# 4-Ethernet.net
KiCad netlist of a schematic drawn in Altium Designer
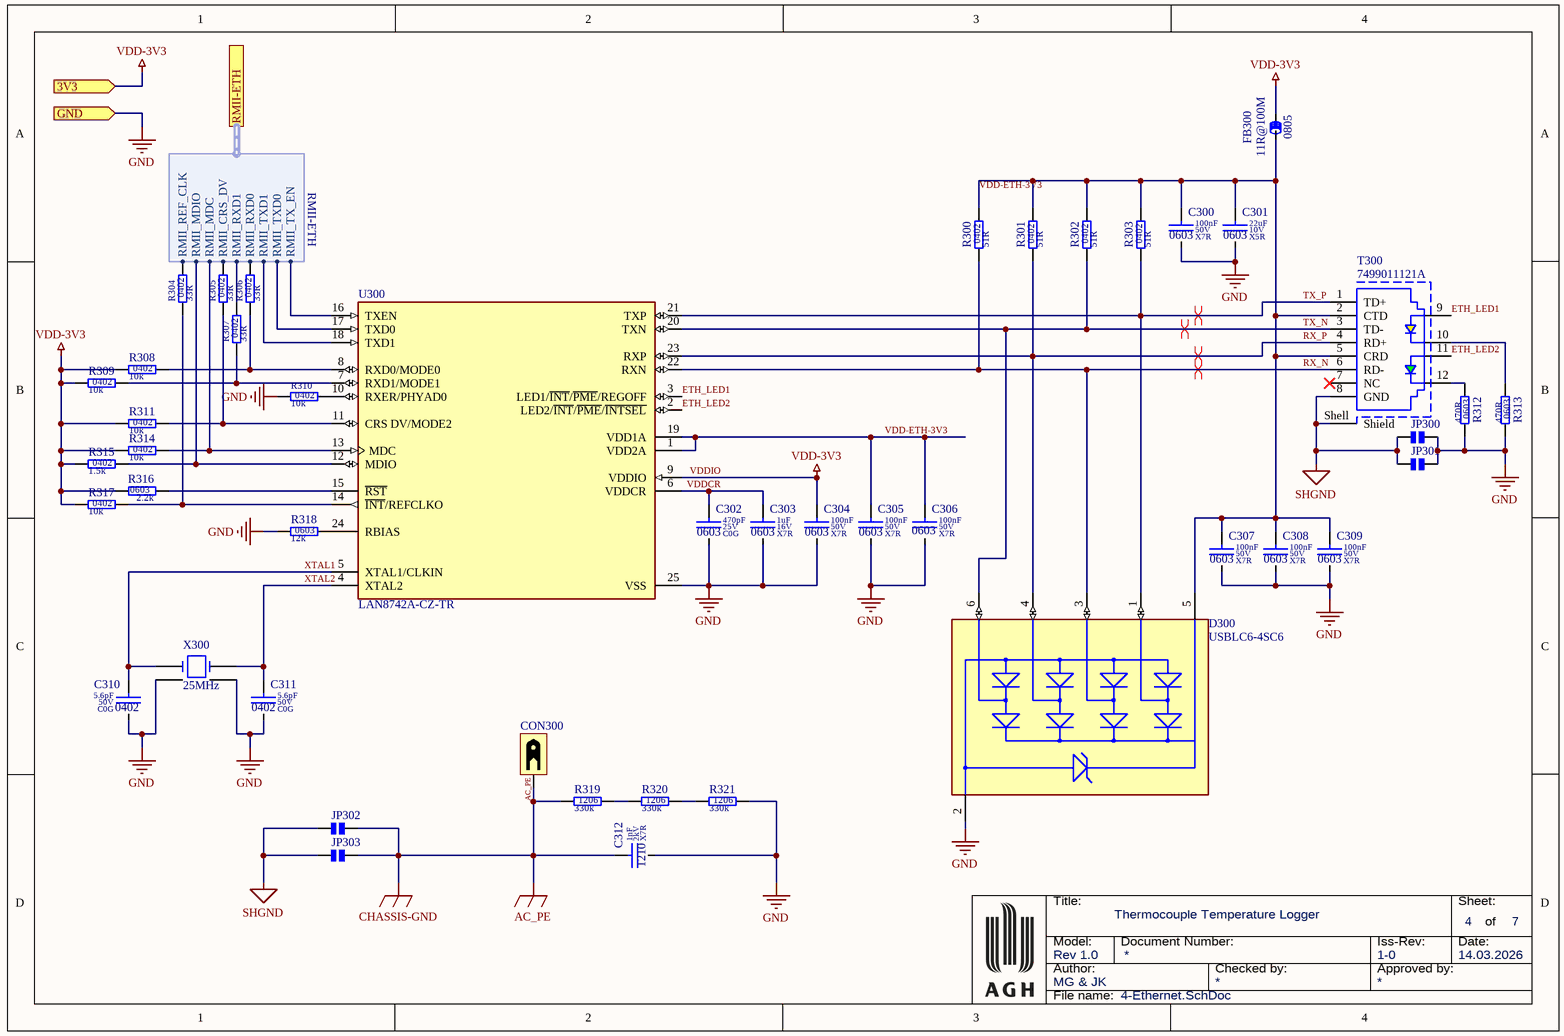
[diagram p0: 4-Ethernet.SchDoc]

(export (version "E")
  (design (tool "Eeschema 10.0.6"))
  (components
    (comp (ref "C300")
      (value "100nF")
      (footprint "C_0603_1608")
      (description "Capacitor")
      (fields
        (field (name "DIELECTRIC") "X7R")
        (field (name "VOLTAGE") "50V")
        (field (name "SCH_FOOTPRINT") "0603")
        (field (name "PART NUMBER") "C_100nF_50V_X7R_0603_10_AECQ1")
        (field (name "MANUFACTURER") "Murata")
      )
      (libsource (lib "Library") (part "C"))
    )
    (comp (ref "C301")
      (value "22uF")
      (footprint "C_0603_1608")
      (description "Capacitor")
      (fields
        (field (name "DIELECTRIC") "X5R")
        (field (name "VOLTAGE") "10V")
        (field (name "SCH_FOOTPRINT") "0603")
        (field (name "PART NUMBER") "C_22uF_10V_X5R_0603_20")
        (field (name "MANUFACTURER") "Murata")
      )
      (libsource (lib "Library") (part "C"))
    )
    (comp (ref "C302")
      (value "470pF")
      (footprint "C_0603_1608")
      (description "Capacitor")
      (fields
        (field (name "DIELECTRIC") "C0G")
        (field (name "VOLTAGE") "25V")
        (field (name "SCH_FOOTPRINT") "0603")
        (field (name "PART NUMBER") "C_470pF_25V_C0G_0603_5")
        (field (name "MANUFACTURER") "Wurth Elektronik")
      )
      (libsource (lib "Library") (part "C"))
    )
    (comp (ref "C303")
      (value "1uF")
      (footprint "C_0603_1608")
      (description "Capacitor")
      (fields
        (field (name "DIELECTRIC") "X7R")
        (field (name "VOLTAGE") "16V")
        (field (name "SCH_FOOTPRINT") "0603")
        (field (name "PART NUMBER") "C_1uF_16V_X7R_0603_10")
        (field (name "MANUFACTURER") "Wurth Elektronik")
      )
      (libsource (lib "Library") (part "C"))
    )
    (comp (ref "C304")
      (value "100nF")
      (footprint "C_0603_1608")
      (description "Capacitor")
      (fields
        (field (name "DIELECTRIC") "X7R")
        (field (name "VOLTAGE") "50V")
        (field (name "SCH_FOOTPRINT") "0603")
        (field (name "PART NUMBER") "C_100nF_50V_X7R_0603_10_AECQ1")
        (field (name "MANUFACTURER") "Murata")
      )
      (libsource (lib "Library") (part "C"))
    )
    (comp (ref "C305")
      (value "100nF")
      (footprint "C_0603_1608")
      (description "Capacitor")
      (fields
        (field (name "DIELECTRIC") "X7R")
        (field (name "VOLTAGE") "50V")
        (field (name "SCH_FOOTPRINT") "0603")
        (field (name "PART NUMBER") "C_100nF_50V_X7R_0603_10_AECQ1")
        (field (name "MANUFACTURER") "Murata")
      )
      (libsource (lib "Library") (part "C"))
    )
    (comp (ref "C306")
      (value "100nF")
      (footprint "C_0603_1608")
      (description "Capacitor")
      (fields
        (field (name "DIELECTRIC") "X7R")
        (field (name "VOLTAGE") "50V")
        (field (name "SCH_FOOTPRINT") "0603")
        (field (name "PART NUMBER") "C_100nF_50V_X7R_0603_10_AECQ1")
        (field (name "MANUFACTURER") "Murata")
      )
      (libsource (lib "Library") (part "C"))
    )
    (comp (ref "C307")
      (value "100nF")
      (footprint "C_0603_1608")
      (description "Capacitor")
      (fields
        (field (name "DIELECTRIC") "X7R")
        (field (name "VOLTAGE") "50V")
        (field (name "SCH_FOOTPRINT") "0603")
        (field (name "PART NUMBER") "C_100nF_50V_X7R_0603_10_AECQ1")
        (field (name "MANUFACTURER") "Murata")
      )
      (libsource (lib "Library") (part "C"))
    )
    (comp (ref "C308")
      (value "100nF")
      (footprint "C_0603_1608")
      (description "Capacitor")
      (fields
        (field (name "DIELECTRIC") "X7R")
        (field (name "VOLTAGE") "50V")
        (field (name "SCH_FOOTPRINT") "0603")
        (field (name "PART NUMBER") "C_100nF_50V_X7R_0603_10_AECQ1")
        (field (name "MANUFACTURER") "Murata")
      )
      (libsource (lib "Library") (part "C"))
    )
    (comp (ref "C309")
      (value "100nF")
      (footprint "C_0603_1608")
      (description "Capacitor")
      (fields
        (field (name "DIELECTRIC") "X7R")
        (field (name "VOLTAGE") "50V")
        (field (name "SCH_FOOTPRINT") "0603")
        (field (name "PART NUMBER") "C_100nF_50V_X7R_0603_10_AECQ1")
        (field (name "MANUFACTURER") "Murata")
      )
      (libsource (lib "Library") (part "C"))
    )
    (comp (ref "C310")
      (value "5.6pF")
      (footprint "C_0402_1005")
      (description "Capacitor")
      (fields
        (field (name "DIELECTRIC") "C0G")
        (field (name "VOLTAGE") "50V")
        (field (name "SCH_FOOTPRINT") "0402")
        (field (name "PART NUMBER") "C_5.6pF_50V_C0G_0402_2_AECQ1")
        (field (name "MANUFACTURER") "Murata")
      )
      (libsource (lib "Library") (part "C"))
    )
    (comp (ref "C311")
      (value "5.6pF")
      (footprint "C_0402_1005")
      (description "Capacitor")
      (fields
        (field (name "DIELECTRIC") "C0G")
        (field (name "VOLTAGE") "50V")
        (field (name "SCH_FOOTPRINT") "0402")
        (field (name "PART NUMBER") "C_5.6pF_50V_C0G_0402_2_AECQ1")
        (field (name "MANUFACTURER") "Murata")
      )
      (libsource (lib "Library") (part "C"))
    )
    (comp (ref "C312")
      (value "1nF")
      (footprint "C_1210_3225")
      (description "Capacitor")
      (fields
        (field (name "DIELECTRIC") "X7R")
        (field (name "VOLTAGE") "2kV")
        (field (name "SCH_FOOTPRINT") "1210")
        (field (name "PART NUMBER") "C_1nF_2kV_X7R_1210_10")
        (field (name "MANUFACTURER") "AVX")
      )
      (libsource (lib "Library") (part "C"))
    )
    (comp (ref "CON300")
      (value "Terminal for PE")
      (footprint "TP_1-726388-2")
      (description "Terminal")
      (fields
        (field (name "PART NUMBER") "TP_TERMINAL_1-726388-2")
        (field (name "MANUFACTURER") "TE Connectivity")
      )
      (libsource (lib "Library") (part "TP_TERMINAL"))
    )
    (comp (ref "D300")
      (value "USBLC6-4SC6")
      (footprint "FP-SOT23-6L-MFG")
      (description "TVS DIODE 5.25V 17V SOT23-6")
      (fields
        (field (name "MANUFACTURER") "STMicroelectronics")
        (field (name "OCTOPART") "https://octopart.com/usblc6-4sc6-stmicroelectronics-347147")
      )
      (libsource (lib "Altium Content Vault") (part "3e70b616ccdc4c88b528e1820c4a7da"))
    )
    (comp (ref "FB300")
      (value "11R@100M")
      (footprint "FB_0805_2012")
      (description "Ferrite Bead")
      (fields
        (field (name "SCH_FOOTPRINT") "0805")
        (field (name "PART NUMBER") "FB_2508051107Y0")
        (field (name "MANUFACTURER") "Fair-Rite")
      )
      (libsource (lib "Library") (part "FB"))
    )
    (comp (ref "JP300")
      (value "Solder Jumper 0603/1608")
      (footprint "JP_0603_1608")
      (fields (field (name "PART NUMBER") "JP_0603_1608"))
      (libsource (lib "Library") (part "JP"))
    )
    (comp (ref "JP301")
      (value "Solder Jumper 0603/1608")
      (footprint "JP_0603_1608")
      (fields (field (name "PART NUMBER") "JP_0603_1608"))
      (libsource (lib "Library") (part "JP"))
    )
    (comp (ref "JP302")
      (value "Solder Jumper 0603/1608")
      (footprint "JP_0603_1608")
      (fields (field (name "PART NUMBER") "JP_0603_1608"))
      (libsource (lib "Library") (part "JP"))
    )
    (comp (ref "JP303")
      (value "Solder Jumper 0603/1608")
      (footprint "JP_0603_1608")
      (fields (field (name "PART NUMBER") "JP_0603_1608"))
      (libsource (lib "Library") (part "JP"))
    )
    (comp (ref "R300")
      (value "51R")
      (footprint "R_0402_1005")
      (fields
        (field (name "SCH_FOOTPRINT") "0402")
        (field (name "PART NUMBER") "R_51R_0402_1_AECQ0")
        (field (name "VOLTAGE") "50V")
        (field (name "POWER") "100mW")
      )
      (libsource (lib "Library") (part "R"))
    )
    (comp (ref "R301")
      (value "51R")
      (footprint "R_0402_1005")
      (fields
        (field (name "SCH_FOOTPRINT") "0402")
        (field (name "PART NUMBER") "R_51R_0402_1_AECQ0")
        (field (name "VOLTAGE") "50V")
        (field (name "POWER") "100mW")
      )
      (libsource (lib "Library") (part "R"))
    )
    (comp (ref "R302")
      (value "51R")
      (footprint "R_0402_1005")
      (fields
        (field (name "SCH_FOOTPRINT") "0402")
        (field (name "PART NUMBER") "R_51R_0402_1_AECQ0")
        (field (name "VOLTAGE") "50V")
        (field (name "POWER") "100mW")
      )
      (libsource (lib "Library") (part "R"))
    )
    (comp (ref "R303")
      (value "51R")
      (footprint "R_0402_1005")
      (fields
        (field (name "SCH_FOOTPRINT") "0402")
        (field (name "PART NUMBER") "R_51R_0402_1_AECQ0")
        (field (name "VOLTAGE") "50V")
        (field (name "POWER") "100mW")
      )
      (libsource (lib "Library") (part "R"))
    )
    (comp (ref "R304")
      (value "33R")
      (footprint "R_0402_1005")
      (fields
        (field (name "SCH_FOOTPRINT") "0402")
        (field (name "PART NUMBER") "R_33R_0402_1_AECQ0")
        (field (name "VOLTAGE") "50V")
        (field (name "POWER") "100mW")
      )
      (libsource (lib "Library") (part "R"))
    )
    (comp (ref "R305")
      (value "33R")
      (footprint "R_0402_1005")
      (fields
        (field (name "SCH_FOOTPRINT") "0402")
        (field (name "PART NUMBER") "R_33R_0402_1_AECQ0")
        (field (name "VOLTAGE") "50V")
        (field (name "POWER") "100mW")
      )
      (libsource (lib "Library") (part "R"))
    )
    (comp (ref "R306")
      (value "33R")
      (footprint "R_0402_1005")
      (fields
        (field (name "SCH_FOOTPRINT") "0402")
        (field (name "PART NUMBER") "R_33R_0402_1_AECQ0")
        (field (name "VOLTAGE") "50V")
        (field (name "POWER") "100mW")
      )
      (libsource (lib "Library") (part "R"))
    )
    (comp (ref "R307")
      (value "33R")
      (footprint "R_0402_1005")
      (fields
        (field (name "SCH_FOOTPRINT") "0402")
        (field (name "PART NUMBER") "R_33R_0402_1_AECQ0")
        (field (name "VOLTAGE") "50V")
        (field (name "POWER") "100mW")
      )
      (libsource (lib "Library") (part "R"))
    )
    (comp (ref "R308")
      (value "10k")
      (footprint "R_0402_1005")
      (fields
        (field (name "SCH_FOOTPRINT") "0402")
        (field (name "PART NUMBER") "R_10k_0402_1")
        (field (name "VOLTAGE") "50V")
        (field (name "POWER") "63mW")
      )
      (libsource (lib "Library") (part "R"))
    )
    (comp (ref "R309")
      (value "10k")
      (footprint "R_0402_1005")
      (fields
        (field (name "SCH_FOOTPRINT") "0402")
        (field (name "PART NUMBER") "R_10k_0402_1")
        (field (name "VOLTAGE") "50V")
        (field (name "POWER") "63mW")
      )
      (libsource (lib "Library") (part "R"))
    )
    (comp (ref "R310")
      (value "10k")
      (footprint "R_0402_1005")
      (fields
        (field (name "SCH_FOOTPRINT") "0402")
        (field (name "PART NUMBER") "R_10k_0402_1")
        (field (name "VOLTAGE") "50V")
        (field (name "POWER") "63mW")
      )
      (libsource (lib "Library") (part "R"))
    )
    (comp (ref "R311")
      (value "10k")
      (footprint "R_0402_1005")
      (fields
        (field (name "SCH_FOOTPRINT") "0402")
        (field (name "PART NUMBER") "R_10k_0402_1")
        (field (name "VOLTAGE") "50V")
        (field (name "POWER") "63mW")
      )
      (libsource (lib "Library") (part "R"))
    )
    (comp (ref "R312")
      (value "470R")
      (footprint "R_0603_1608")
      (fields
        (field (name "SCH_FOOTPRINT") "0603")
        (field (name "PART NUMBER") "R_470R_0603_1")
        (field (name "VOLTAGE") "50V")
        (field (name "POWER") "100mW")
      )
      (libsource (lib "Library") (part "R"))
    )
    (comp (ref "R313")
      (value "470R")
      (footprint "R_0603_1608")
      (fields
        (field (name "SCH_FOOTPRINT") "0603")
        (field (name "PART NUMBER") "R_470R_0603_1")
        (field (name "VOLTAGE") "50V")
        (field (name "POWER") "100mW")
      )
      (libsource (lib "Library") (part "R"))
    )
    (comp (ref "R314")
      (value "10k")
      (footprint "R_0402_1005")
      (fields
        (field (name "SCH_FOOTPRINT") "0402")
        (field (name "PART NUMBER") "R_10k_0402_1")
        (field (name "VOLTAGE") "50V")
        (field (name "POWER") "63mW")
      )
      (libsource (lib "Library") (part "R"))
    )
    (comp (ref "R315")
      (value "1.5k")
      (footprint "R_0402_1005")
      (fields
        (field (name "SCH_FOOTPRINT") "0402")
        (field (name "PART NUMBER") "R_1.5k_0402_1_AECQ0")
        (field (name "VOLTAGE") "50V")
        (field (name "POWER") "100mW")
      )
      (libsource (lib "Library") (part "R"))
    )
    (comp (ref "R316")
      (value "2.2k")
      (footprint "R_0603_1608")
      (fields
        (field (name "SCH_FOOTPRINT") "0603")
        (field (name "PART NUMBER") "R_2.2k_0603_1")
        (field (name "VOLTAGE") "50V")
        (field (name "POWER") "100mW")
      )
      (libsource (lib "Library") (part "R"))
    )
    (comp (ref "R317")
      (value "10k")
      (footprint "R_0402_1005")
      (fields
        (field (name "SCH_FOOTPRINT") "0402")
        (field (name "PART NUMBER") "R_10k_0402_1")
        (field (name "VOLTAGE") "50V")
        (field (name "POWER") "63mW")
      )
      (libsource (lib "Library") (part "R"))
    )
    (comp (ref "R318")
      (value "12k")
      (footprint "R_0603_1608")
      (fields
        (field (name "SCH_FOOTPRINT") "0603")
        (field (name "PART NUMBER") "R_12k_0603_1")
        (field (name "VOLTAGE") "50V")
        (field (name "POWER") "100mW")
      )
      (libsource (lib "Library") (part "R"))
    )
    (comp (ref "R319")
      (value "330k")
      (footprint "R_1206_3216")
      (fields
        (field (name "SCH_FOOTPRINT") "1206")
        (field (name "PART NUMBER") "R_330k_1206_1")
        (field (name "VOLTAGE") "200V")
        (field (name "POWER") "250mW")
      )
      (libsource (lib "Library") (part "R"))
    )
    (comp (ref "R320")
      (value "330k")
      (footprint "R_1206_3216")
      (fields
        (field (name "SCH_FOOTPRINT") "1206")
        (field (name "PART NUMBER") "R_330k_1206_1")
        (field (name "VOLTAGE") "200V")
        (field (name "POWER") "250mW")
      )
      (libsource (lib "Library") (part "R"))
    )
    (comp (ref "R321")
      (value "330k")
      (footprint "R_1206_3216")
      (fields
        (field (name "SCH_FOOTPRINT") "1206")
        (field (name "PART NUMBER") "R_330k_1206_1")
        (field (name "VOLTAGE") "200V")
        (field (name "POWER") "250mW")
      )
      (libsource (lib "Library") (part "R"))
    )
    (comp (ref "T300")
      (value "7499011121A")
      (footprint "7499011121A")
      (description "WE-RJ45 LAN Transformer, THT, 10/100 Base-T, Tab Down, 1 Port")
      (fields (field (name "MANUFACTURER") "Wurth Elektronik"))
      (libsource (lib "Altium_WE-RJ45 LAN (rev25d)") (part "7499011121A"))
    )
    (comp (ref "U300")
      (value "LAN8742A-CZ-TR")
      (footprint "FP-C04-143B-S4QFN-MFG")
      (description "IC TRANSCEIVER 1/1 24SQFN")
      (fields
        (field (name "MANUFACTURER") "Microchip")
        (field (name "OCTOPART") "https://octopart.com/lan8742a-cz-tr-microchip-29030587")
      )
      (libsource (lib "Altium Content Vault") (part "83151231c1ada07e85dcda6cce77793"))
    )
    (comp (ref "X300")
      (value "25MHz")
      (footprint "X_2x1.6_4PIN")
      (fields
        (field (name "PART NUMBER") "NX2016SA-25.000M-STD-CZS-1")
        (field (name "MANUFACTURER") "NDK")
        (field (name "Comment") "32 MHz Oscilator")
      )
      (libsource (lib "Library") (part "X_GENERIC_4PIN"))
    )
  )
  (nets
    (net (code "2") (name "/ETH_LED1") (class "Default")
      (node (ref "T300") (pin "9") (pinfunction "9_9") (pintype "passive"))
      (node (ref "U300") (pin "3") (pinfunction "LED1/~{INT}/~{PME}/REGOFF_3") (pintype "bidirectional"))
    )
    (net (code "3") (name "/ETH_LED2") (class "Default")
      (node (ref "T300") (pin "11") (pinfunction "11_11") (pintype "passive"))
      (node (ref "U300") (pin "2") (pinfunction "LED2/~{INT}/~{PME}/~{INTSEL}_2") (pintype "bidirectional"))
    )
    (net (code "4") (name "/RMII_CRS_DV") (class "Default")
      (node (ref "R305") (pin "2") (pinfunction "2_2") (pintype "passive"))
    )
    (net (code "5") (name "/RMII_MDC") (class "Default")
      (node (ref "R314") (pin "2") (pinfunction "2_2") (pintype "passive"))
      (node (ref "U300") (pin "13") (pinfunction "MDC_13") (pintype "input"))
    )
    (net (code "6") (name "/RMII_MDIO") (class "Default")
      (node (ref "R315") (pin "2") (pinfunction "2_2") (pintype "passive"))
      (node (ref "U300") (pin "12") (pinfunction "MDIO_12") (pintype "bidirectional"))
    )
    (net (code "7") (name "/RMII_REF_CLK") (class "Default")
      (node (ref "R304") (pin "2") (pinfunction "2_2") (pintype "passive"))
    )
    (net (code "8") (name "/RMII_RXD0") (class "Default")
      (node (ref "R306") (pin "2") (pinfunction "2_2") (pintype "passive"))
    )
    (net (code "9") (name "/RMII_RXD1") (class "Default")
      (node (ref "R307") (pin "2") (pinfunction "2_2") (pintype "passive"))
    )
    (net (code "10") (name "/RMII_TXD0") (class "Default")
      (node (ref "U300") (pin "17") (pinfunction "TXD0_17") (pintype "input"))
    )
    (net (code "11") (name "/RMII_TXD1") (class "Default")
      (node (ref "U300") (pin "18") (pinfunction "TXD1_18") (pintype "input"))
    )
    (net (code "12") (name "/RMII_TX_EN") (class "Default")
      (node (ref "U300") (pin "16") (pinfunction "TXEN_16") (pintype "input"))
    )
    (net (code "13") (name "/RX_N") (class "Default")
      (node (ref "D300") (pin "3") (pinfunction "I/O2_3") (pintype "bidirectional"))
      (node (ref "R300") (pin "1") (pinfunction "1_1") (pintype "passive"))
      (node (ref "T300") (pin "6") (pinfunction "RD-_6") (pintype "passive"))
      (node (ref "U300") (pin "22") (pinfunction "RXN_22") (pintype "bidirectional"))
    )
    (net (code "14") (name "/RX_P") (class "Default")
      (node (ref "D300") (pin "4") (pinfunction "I/O3_4") (pintype "bidirectional"))
      (node (ref "R301") (pin "1") (pinfunction "1_1") (pintype "passive"))
      (node (ref "T300") (pin "4") (pinfunction "RD+_4") (pintype "passive"))
      (node (ref "U300") (pin "23") (pinfunction "RXP_23") (pintype "bidirectional"))
    )
    (net (code "15") (name "/TX_N") (class "Default")
      (node (ref "D300") (pin "6") (pinfunction "I/O4_6") (pintype "bidirectional"))
      (node (ref "R302") (pin "1") (pinfunction "1_1") (pintype "passive"))
      (node (ref "T300") (pin "3") (pinfunction "TD-_3") (pintype "passive"))
      (node (ref "U300") (pin "20") (pinfunction "TXN_20") (pintype "bidirectional"))
    )
    (net (code "16") (name "/TX_P") (class "Default")
      (node (ref "D300") (pin "1") (pinfunction "I/O1_1") (pintype "bidirectional"))
      (node (ref "R303") (pin "1") (pinfunction "1_1") (pintype "passive"))
      (node (ref "T300") (pin "1") (pinfunction "TD+_1") (pintype "passive"))
      (node (ref "U300") (pin "21") (pinfunction "TXP_21") (pintype "bidirectional"))
    )
    (net (code "17") (name "/VDD-ETH-3V3") (class "Default")
      (node (ref "C300") (pin "1") (pinfunction "1_1") (pintype "passive"))
      (node (ref "C301") (pin "1") (pinfunction "1_1") (pintype "passive"))
      (node (ref "C305") (pin "1") (pinfunction "1_1") (pintype "passive"))
      (node (ref "C306") (pin "1") (pinfunction "1_1") (pintype "passive"))
      (node (ref "C307") (pin "1") (pinfunction "1_1") (pintype "passive"))
      (node (ref "C308") (pin "1") (pinfunction "1_1") (pintype "passive"))
      (node (ref "C309") (pin "1") (pinfunction "1_1") (pintype "passive"))
      (node (ref "D300") (pin "5") (pinfunction "VBUS_5") (pintype "power_in"))
      (node (ref "FB300") (pin "2") (pintype "passive"))
      (node (ref "R300") (pin "2") (pinfunction "2_2") (pintype "passive"))
      (node (ref "R301") (pin "2") (pinfunction "2_2") (pintype "passive"))
      (node (ref "R302") (pin "2") (pinfunction "2_2") (pintype "passive"))
      (node (ref "R303") (pin "2") (pinfunction "2_2") (pintype "passive"))
      (node (ref "T300") (pin "2") (pinfunction "CTD_2") (pintype "passive"))
      (node (ref "T300") (pin "5") (pinfunction "CRD_5") (pintype "passive"))
      (node (ref "U300") (pin "1") (pinfunction "VDD2A_1") (pintype "power_in"))
      (node (ref "U300") (pin "19") (pinfunction "VDD1A_19") (pintype "power_in"))
    )
    (net (code "18") (name "/VDDCR") (class "Default")
      (node (ref "C302") (pin "1") (pinfunction "1_1") (pintype "passive"))
      (node (ref "C303") (pin "1") (pinfunction "1_1") (pintype "passive"))
      (node (ref "U300") (pin "6") (pinfunction "VDDCR_6") (pintype "power_in"))
    )
    (net (code "19") (name "/XTAL1") (class "Default")
      (node (ref "C310") (pin "1") (pinfunction "1_1") (pintype "passive"))
      (node (ref "U300") (pin "5") (pinfunction "XTAL1/CLKIN_5") (pintype "passive"))
      (node (ref "X300") (pin "3") (pinfunction "3_3") (pintype "passive"))
    )
    (net (code "20") (name "/XTAL2") (class "Default")
      (node (ref "C311") (pin "1") (pinfunction "1_1") (pintype "passive"))
      (node (ref "U300") (pin "4") (pinfunction "XTAL2_4") (pintype "passive"))
      (node (ref "X300") (pin "1") (pinfunction "1_1") (pintype "passive"))
    )
    (net (code "22") (name "AC_PE") (class "Default")
      (node (ref "C312") (pin "1") (pinfunction "1_1") (pintype "passive"))
      (node (ref "CON300") (pin "1") (pinfunction "TP_1") (pintype "passive"))
      (node (ref "JP302") (pin "2") (pinfunction "2_2") (pintype "passive"))
      (node (ref "JP303") (pin "2") (pinfunction "2_2") (pintype "passive"))
      (node (ref "R319") (pin "1") (pinfunction "1_1") (pintype "passive"))
    )
    (net (code "23") (name "GND") (class "Default")
      (node (ref "C300") (pin "2") (pinfunction "2_2") (pintype "passive"))
      (node (ref "C301") (pin "2") (pinfunction "2_2") (pintype "passive"))
      (node (ref "C302") (pin "2") (pinfunction "2_2") (pintype "passive"))
      (node (ref "C303") (pin "2") (pinfunction "2_2") (pintype "passive"))
      (node (ref "C304") (pin "2") (pinfunction "2_2") (pintype "passive"))
      (node (ref "C305") (pin "2") (pinfunction "2_2") (pintype "passive"))
      (node (ref "C306") (pin "2") (pinfunction "2_2") (pintype "passive"))
      (node (ref "C307") (pin "2") (pinfunction "2_2") (pintype "passive"))
      (node (ref "C308") (pin "2") (pinfunction "2_2") (pintype "passive"))
      (node (ref "C309") (pin "2") (pinfunction "2_2") (pintype "passive"))
      (node (ref "C310") (pin "2") (pinfunction "2_2") (pintype "passive"))
      (node (ref "C311") (pin "2") (pinfunction "2_2") (pintype "passive"))
      (node (ref "C312") (pin "2") (pinfunction "2_2") (pintype "passive"))
      (node (ref "D300") (pin "2") (pinfunction "GND_2") (pintype "passive"))
      (node (ref "JP300") (pin "2") (pinfunction "2_2") (pintype "passive"))
      (node (ref "JP301") (pin "2") (pinfunction "2_2") (pintype "passive"))
      (node (ref "R310") (pin "1") (pinfunction "1_1") (pintype "passive"))
      (node (ref "R312") (pin "1") (pinfunction "1_1") (pintype "passive"))
      (node (ref "R313") (pin "1") (pinfunction "1_1") (pintype "passive"))
      (node (ref "R318") (pin "1") (pinfunction "1_1") (pintype "passive"))
      (node (ref "R321") (pin "2") (pinfunction "2_2") (pintype "passive"))
      (node (ref "U300") (pin "25") (pinfunction "VSS_25") (pintype "passive"))
      (node (ref "X300") (pin "2") (pinfunction "GND_2") (pintype "passive"))
      (node (ref "X300") (pin "4") (pinfunction "GND_4") (pintype "passive"))
    )
    (net (code "24") (name "Net-(R312-Pad2)") (class "Default")
      (node (ref "R312") (pin "2") (pinfunction "2_2") (pintype "passive"))
      (node (ref "T300") (pin "12") (pinfunction "12_12") (pintype "passive"))
    )
    (net (code "25") (name "Net-(R313-Pad2)") (class "Default")
      (node (ref "R313") (pin "2") (pinfunction "2_2") (pintype "passive"))
      (node (ref "T300") (pin "10") (pinfunction "10_10") (pintype "passive"))
    )
    (net (code "26") (name "Net-(R319-Pad2)") (class "Default")
      (node (ref "R319") (pin "2") (pinfunction "2_2") (pintype "passive"))
      (node (ref "R320") (pin "1") (pinfunction "1_1") (pintype "passive"))
    )
    (net (code "27") (name "Net-(R320-Pad2)") (class "Default")
      (node (ref "R320") (pin "2") (pinfunction "2_2") (pintype "passive"))
      (node (ref "R321") (pin "1") (pinfunction "1_1") (pintype "passive"))
    )
    (net (code "28") (name "Net-(U300-CRS_DV{slash}MODE2)") (class "Default")
      (node (ref "R305") (pin "1") (pinfunction "1_1") (pintype "passive"))
      (node (ref "R311") (pin "2") (pinfunction "2_2") (pintype "passive"))
      (node (ref "U300") (pin "11") (pinfunction "CRS_DV/MODE2_11") (pintype "bidirectional"))
    )
    (net (code "29") (name "Net-(U300-RBIAS)") (class "Default")
      (node (ref "R318") (pin "2") (pinfunction "2_2") (pintype "passive"))
      (node (ref "U300") (pin "24") (pinfunction "RBIAS_24") (pintype "passive"))
    )
    (net (code "30") (name "Net-(U300-RXD0{slash}MODE0)") (class "Default")
      (node (ref "R306") (pin "1") (pinfunction "1_1") (pintype "passive"))
      (node (ref "R308") (pin "2") (pinfunction "2_2") (pintype "passive"))
      (node (ref "U300") (pin "8") (pinfunction "RXD0/MODE0_8") (pintype "bidirectional"))
    )
    (net (code "31") (name "Net-(U300-RXD1{slash}MODE1)") (class "Default")
      (node (ref "R307") (pin "1") (pinfunction "1_1") (pintype "passive"))
      (node (ref "R309") (pin "2") (pinfunction "2_2") (pintype "passive"))
      (node (ref "U300") (pin "7") (pinfunction "RXD1/MODE1_7") (pintype "bidirectional"))
    )
    (net (code "32") (name "Net-(U300-RXER{slash}PHYAD0)") (class "Default")
      (node (ref "R310") (pin "2") (pinfunction "2_2") (pintype "passive"))
      (node (ref "U300") (pin "10") (pinfunction "RXER/PHYAD0_10") (pintype "bidirectional"))
    )
    (net (code "33") (name "Net-(U300-~{INT}{slash}REFCLKO)") (class "Default")
      (node (ref "R304") (pin "1") (pinfunction "1_1") (pintype "passive"))
      (node (ref "R317") (pin "2") (pinfunction "2_2") (pintype "passive"))
      (node (ref "U300") (pin "14") (pinfunction "~{INT}/REFCLKO_14") (pintype "output"))
    )
    (net (code "34") (name "Net-(U300-~{RST})") (class "Default")
      (node (ref "R316") (pin "1") (pinfunction "1_1") (pintype "passive"))
      (node (ref "U300") (pin "15") (pinfunction "~{RST}_15") (pintype "passive"))
    )
    (net (code "35") (name "SHGND") (class "Default")
      (node (ref "JP300") (pin "1") (pinfunction "1_1") (pintype "passive"))
      (node (ref "JP301") (pin "1") (pinfunction "1_1") (pintype "passive"))
      (node (ref "JP302") (pin "1") (pinfunction "1_1") (pintype "passive"))
      (node (ref "JP303") (pin "1") (pinfunction "1_1") (pintype "passive"))
      (node (ref "T300") (pin "8") (pinfunction "GND_8") (pintype "passive"))
      (node (ref "T300") (pin "Shell") (pinfunction "Shield_Shell") (pintype "passive"))
    )
    (net (code "36") (name "VDD-3V3") (class "Default")
      (node (ref "C304") (pin "1") (pinfunction "1_1") (pintype "passive"))
      (node (ref "FB300") (pin "1") (pintype "passive"))
      (node (ref "R308") (pin "1") (pinfunction "1_1") (pintype "passive"))
      (node (ref "R309") (pin "1") (pinfunction "1_1") (pintype "passive"))
      (node (ref "R311") (pin "1") (pinfunction "1_1") (pintype "passive"))
      (node (ref "R314") (pin "1") (pinfunction "1_1") (pintype "passive"))
      (node (ref "R315") (pin "1") (pinfunction "1_1") (pintype "passive"))
      (node (ref "R316") (pin "2") (pinfunction "2_2") (pintype "passive"))
      (node (ref "R317") (pin "1") (pinfunction "1_1") (pintype "passive"))
      (node (ref "U300") (pin "9") (pinfunction "VDDIO_9") (pintype "input"))
    )
    (net (code "37") (name "unconnected-(T300-NC-Pad7)") (class "Default")
      (node (ref "T300") (pin "7") (pinfunction "NC_7") (pintype "passive+no_connect"))
    )
  )
)
